# 5050LED.net
KiCad netlist of a schematic drawn in EAGLE
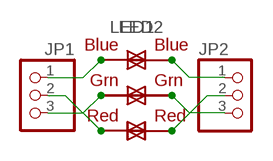
[diagram p0: schematic, sheet 1]

(export (version "E")
  (design (tool "Eeschema 10.0.6"))
  (components
    (comp (ref "JP1")
      (value "PINHD-1X3CB")
      (footprint "eagle-import:1X03-CLEANBIG")
      (libsource (lib "eagle-import") (part "PINHD-1X3CB"))
    )
    (comp (ref "JP2")
      (value "PINHD-1X3CB")
      (footprint "eagle-import:1X03-CLEANBIG")
      (libsource (lib "eagle-import") (part "PINHD-1X3CB"))
    )
    (comp (ref "LED1")
      (value "RGBLED5050")
      (footprint "eagle-import:RGBLED5050")
      (libsource (lib "eagle-import") (part "RGBLED5050"))
    )
    (comp (ref "LED2")
      (value "RGBLED5050")
      (footprint "eagle-import:RGBLED5050")
      (libsource (lib "eagle-import") (part "RGBLED5050"))
    )
  )
  (nets
    (net (code "1") (name "Net-(LED1-BLUE_A)") (class "Default")
      (node (ref "JP1") (pin "1") (pinfunction "1_1") (pintype "passive"))
      (node (ref "LED1") (pin "3") (pinfunction "BLUE_A_3") (pintype "bidirectional"))
      (node (ref "LED2") (pin "4") (pinfunction "BLUE_C_4") (pintype "bidirectional"))
    )
    (net (code "2") (name "Net-(LED1-BLUE_C)") (class "Default")
      (node (ref "JP2") (pin "1") (pinfunction "1_1") (pintype "passive"))
      (node (ref "LED1") (pin "4") (pinfunction "BLUE_C_4") (pintype "bidirectional"))
      (node (ref "LED2") (pin "3") (pinfunction "BLUE_A_3") (pintype "bidirectional"))
    )
    (net (code "3") (name "Net-(LED1-GREEN_A)") (class "Default")
      (node (ref "JP1") (pin "3") (pinfunction "3_3") (pintype "passive"))
      (node (ref "LED1") (pin "1") (pinfunction "GREEN_A_1") (pintype "bidirectional"))
      (node (ref "LED2") (pin "6") (pinfunction "GREEN_C_6") (pintype "bidirectional"))
    )
    (net (code "4") (name "Net-(LED1-GREEN_C)") (class "Default")
      (node (ref "JP2") (pin "3") (pinfunction "3_3") (pintype "passive"))
      (node (ref "LED1") (pin "6") (pinfunction "GREEN_C_6") (pintype "bidirectional"))
      (node (ref "LED2") (pin "1") (pinfunction "GREEN_A_1") (pintype "bidirectional"))
    )
    (net (code "5") (name "Net-(LED1-RED_A)") (class "Default")
      (node (ref "JP1") (pin "2") (pinfunction "2_2") (pintype "passive"))
      (node (ref "LED1") (pin "2") (pinfunction "RED_A_2") (pintype "bidirectional"))
      (node (ref "LED2") (pin "5") (pinfunction "RED_C_5") (pintype "bidirectional"))
    )
    (net (code "6") (name "Net-(LED1-RED_C)") (class "Default")
      (node (ref "JP2") (pin "2") (pinfunction "2_2") (pintype "passive"))
      (node (ref "LED1") (pin "5") (pinfunction "RED_C_5") (pintype "bidirectional"))
      (node (ref "LED2") (pin "2") (pinfunction "RED_A_2") (pintype "bidirectional"))
    )
  )
)
